# power_management.net
KiCad netlist of a schematic drawn in Altium Designer
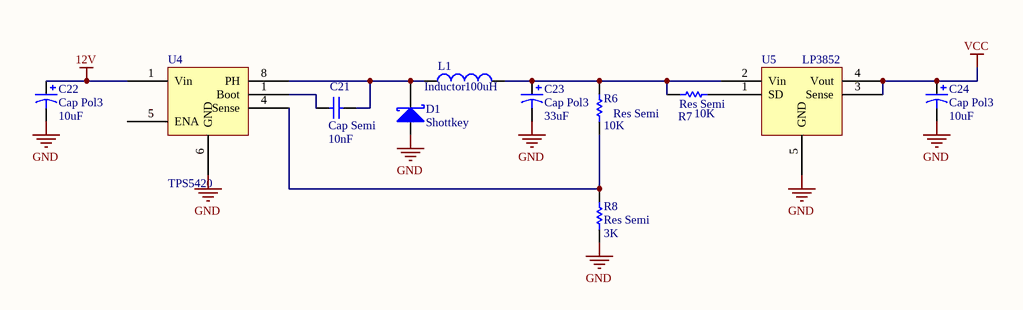
[diagram p0: power_management.SchDoc]

(export (version "E")
  (design (tool "Eeschema 10.0.6"))
  (components
    (comp (ref "C21")
      (value "Cap Semi")
      (footprint "C0805")
      (description "Capacitor (Semiconductor SIM Model)")
      (fields (field (name "ALTIUM_VALUE") "10nF") (field (name "PUBLISHER") "Altium Limited"))
      (libsource (lib "Miscellaneous Devices") (part "Cap Semi"))
    )
    (comp (ref "C22")
      (value "Cap Pol3")
      (footprint "TC6032-2412")
      (description "Polarized Capacitor (Surface Mount)")
      (fields (field (name "ALTIUM_VALUE") "10uF") (field (name "PUBLISHER") "Altium Limited"))
      (libsource (lib "Miscellaneous Devices") (part "Cap Pol3"))
    )
    (comp (ref "C23")
      (value "Cap Pol3")
      (footprint "TC6032-2412")
      (description "Polarized Capacitor (Surface Mount)")
      (fields (field (name "ALTIUM_VALUE") "33uF") (field (name "PUBLISHER") "Altium Limited"))
      (libsource (lib "Miscellaneous Devices") (part "Cap Pol3"))
    )
    (comp (ref "C24")
      (value "Cap Pol3")
      (footprint "TC3216-1206")
      (description "Polarized Capacitor (Surface Mount)")
      (fields (field (name "ALTIUM_VALUE") "10uF") (field (name "PUBLISHER") "Altium Limited"))
      (libsource (lib "Miscellaneous Devices") (part "Cap Pol3"))
    )
    (comp (ref "D1")
      (value "Shottkey")
      (footprint "TO-220AC")
      (description "Schottky Rectifier")
      (fields (field (name "PUBLISHER") "Altium Limited"))
      (libsource (lib "Miscellaneous Devices") (part "Diode 10TQ035"))
    )
    (comp (ref "L1")
      (value "Inductor")
      (footprint "SB_IND")
      (fields (field (name "ALTIUM_VALUE") "100uH") (field (name "PUBLISHER") "Altium Limited"))
      (libsource (lib "Miscellaneous Devices") (part "Inductor"))
    )
    (comp (ref "R6")
      (value "Res Semi")
      (footprint "RESC2012L")
      (description "Semiconductor Resistor")
      (fields (field (name "ALTIUM_VALUE") "10K") (field (name "PUBLISHER") "Altium Limited"))
      (libsource (lib "Miscellaneous Devices") (part "Res Semi"))
    )
    (comp (ref "R7")
      (value "Res Semi")
      (footprint "RESC2012L")
      (description "Semiconductor Resistor")
      (fields (field (name "ALTIUM_VALUE") "10K") (field (name "PUBLISHER") "Altium Limited"))
      (libsource (lib "Miscellaneous Devices") (part "Res Semi"))
    )
    (comp (ref "R8")
      (value "Res Semi")
      (footprint "RESC2012L")
      (description "Semiconductor Resistor")
      (fields (field (name "ALTIUM_VALUE") "3K") (field (name "PUBLISHER") "Altium Limited"))
      (libsource (lib "Miscellaneous Devices") (part "Res Semi"))
    )
    (comp (ref "U4")
      (value "TPS5420")
      (footprint "SO8_N")
      (description "2A Wide Input Range Step-Down Swift Converter")
      (libsource (lib "Sonar_board") (part "TPS5420"))
    )
    (comp (ref "U5")
      (value "LP3852")
      (footprint "SOT223-5N")
      (description "1.5A Fast Response Ultra Low Dropout Linear Regulator")
      (libsource (lib "Sonar_board") (part "LP3852"))
    )
  )
  (nets
    (net (code "1") (name "12V") (class "Default")
      (node (ref "C22") (pin "1") (pinfunction "1_1") (pintype "passive"))
      (node (ref "U4") (pin "1") (pinfunction "Vin_1") (pintype "passive"))
    )
    (net (code "2") (name "GND") (class "Default")
      (node (ref "C22") (pin "2") (pinfunction "2_2") (pintype "passive"))
      (node (ref "C23") (pin "2") (pinfunction "2_2") (pintype "passive"))
      (node (ref "C24") (pin "2") (pinfunction "2_2") (pintype "passive"))
      (node (ref "R8") (pin "1") (pinfunction "1_1") (pintype "passive"))
      (node (ref "U4") (pin "6") (pinfunction "GND_6") (pintype "passive"))
      (node (ref "U5") (pin "5") (pinfunction "GND_5") (pintype "passive"))
    )
    (net (code "3") (name "Net-(D1-K)") (class "Default")
      (node (ref "C21") (pin "2") (pinfunction "2_2") (pintype "passive"))
      (node (ref "D1") (pin "1") (pinfunction "K_1") (pintype "passive"))
      (node (ref "L1") (pin "1") (pinfunction "1_1") (pintype "passive"))
      (node (ref "U4") (pin "8") (pinfunction "PH_8") (pintype "passive"))
    )
    (net (code "4") (name "Net-(U4-Boot)") (class "Default")
      (node (ref "C21") (pin "1") (pinfunction "1_1") (pintype "passive"))
      (node (ref "U4") (pin "1") (pinfunction "Boot_1") (pintype "passive"))
    )
    (net (code "5") (name "Net-(U4-Sense)") (class "Default")
      (node (ref "R6") (pin "1") (pinfunction "1_1") (pintype "passive"))
      (node (ref "R8") (pin "2") (pinfunction "2_2") (pintype "passive"))
      (node (ref "U4") (pin "4") (pinfunction "Sense_4") (pintype "passive"))
    )
    (net (code "6") (name "Net-(U5-SD)") (class "Default")
      (node (ref "R7") (pin "2") (pinfunction "2_2") (pintype "passive"))
      (node (ref "U5") (pin "1") (pinfunction "SD_1") (pintype "passive"))
    )
    (net (code "7") (name "Net-(U5-Vin)") (class "Default")
      (node (ref "C23") (pin "1") (pinfunction "1_1") (pintype "passive"))
      (node (ref "L1") (pin "2") (pinfunction "2_2") (pintype "passive"))
      (node (ref "R6") (pin "2") (pinfunction "2_2") (pintype "passive"))
      (node (ref "R7") (pin "1") (pinfunction "1_1") (pintype "passive"))
      (node (ref "U5") (pin "2") (pinfunction "Vin_2") (pintype "passive"))
    )
    (net (code "8") (name "VCC") (class "Default")
      (node (ref "C24") (pin "1") (pinfunction "1_1") (pintype "passive"))
      (node (ref "U5") (pin "3") (pinfunction "Sense_3") (pintype "passive"))
      (node (ref "U5") (pin "4") (pinfunction "Vout_4") (pintype "passive"))
    )
    (net (code "9") (name "unconnected-(D1-A-Pad3)") (class "Default")
      (node (ref "D1") (pin "3") (pinfunction "A_3") (pintype "passive"))
    )
    (net (code "10") (name "unconnected-(U4-ENA-Pad5)") (class "Default")
      (node (ref "U4") (pin "5") (pinfunction "ENA_5") (pintype "passive"))
    )
  )
)
